# EFIS.net
KiCad netlist of a schematic drawn in EAGLE
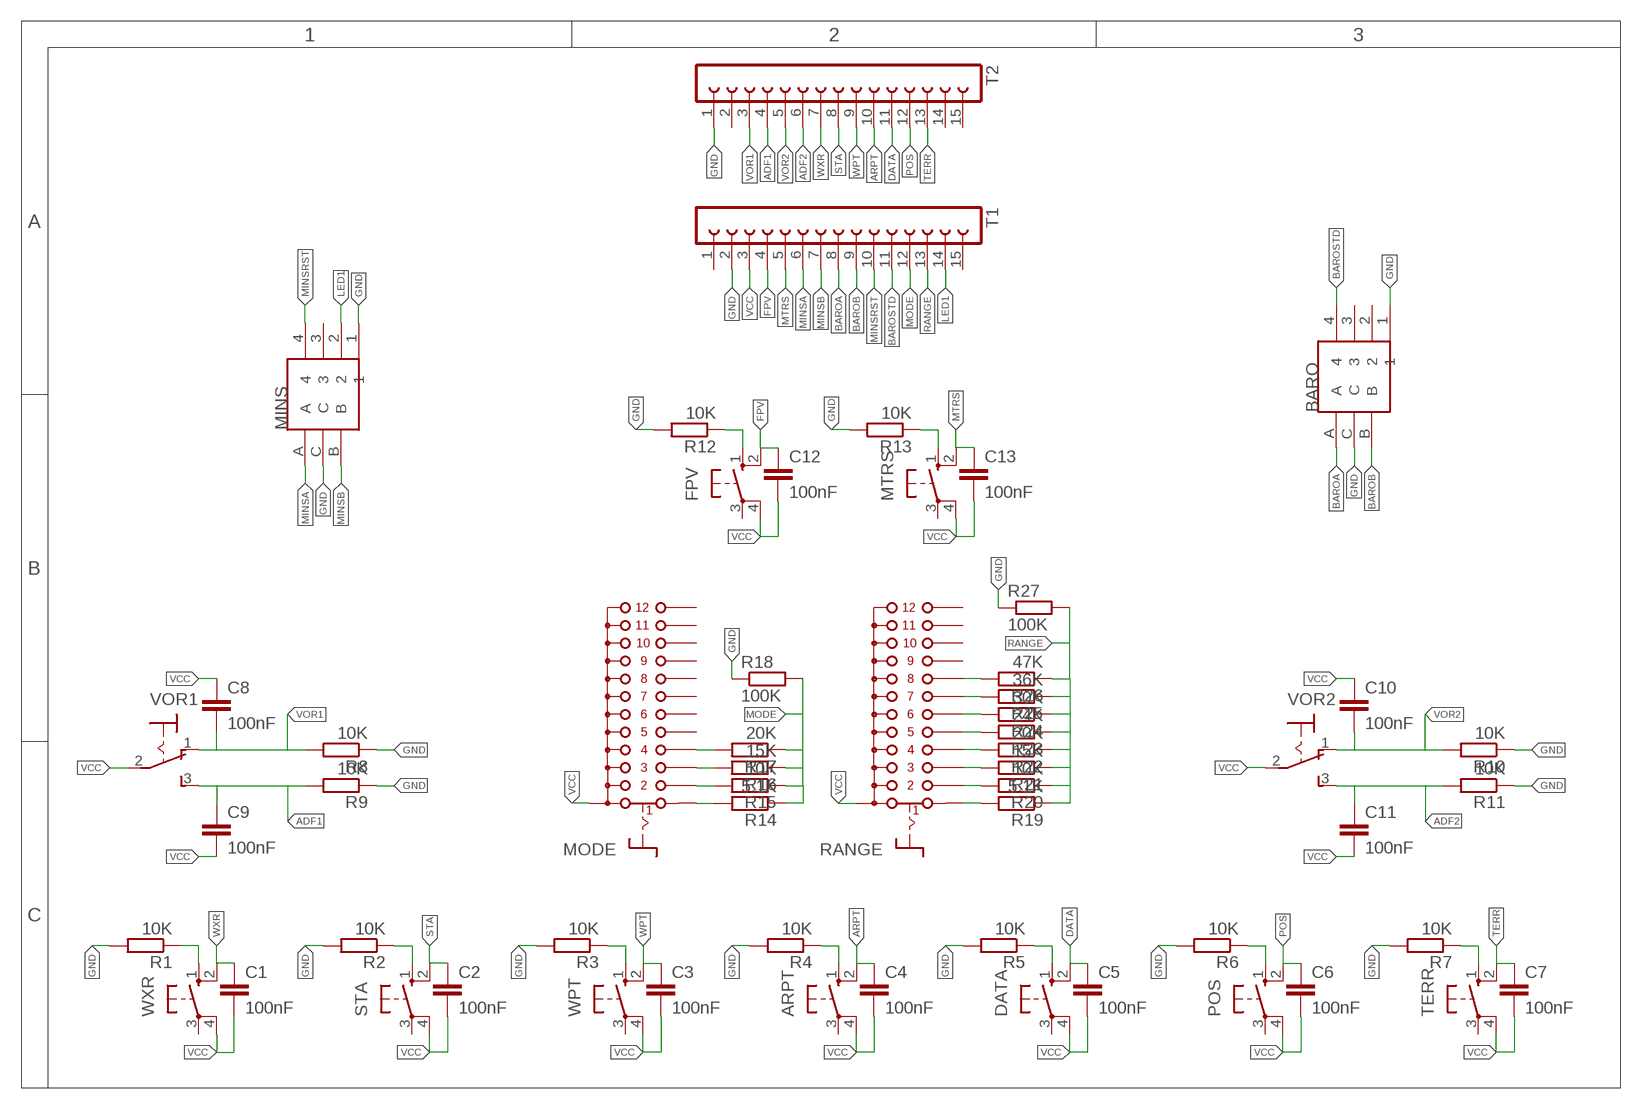
[diagram p0: schematic, sheet 1]

(export (version "E")
  (design (tool "Eeschema 10.0.6"))
  (components
    (comp (ref "ARPT")
      (value "10-XX")
      (footprint "eagle-import:B3F-10XX")
      (fields (field (name "MPN") "B3F-1000"))
      (libsource (lib "eagle-import") (part "10-XX"))
    )
    (comp (ref "BARO")
      (value "MERP12246GR")
      (footprint "eagle-import:MERP1224126")
      (libsource (lib "eagle-import") (part "MERP12246GR"))
    )
    (comp (ref "C1")
      (value "100nF")
      (footprint "eagle-import:C1206")
      (libsource (lib "eagle-import") (part "C-EUC1206"))
    )
    (comp (ref "C2")
      (value "100nF")
      (footprint "eagle-import:C1206")
      (libsource (lib "eagle-import") (part "C-EUC1206"))
    )
    (comp (ref "C3")
      (value "100nF")
      (footprint "eagle-import:C1206")
      (libsource (lib "eagle-import") (part "C-EUC1206"))
    )
    (comp (ref "C4")
      (value "100nF")
      (footprint "eagle-import:C1206")
      (libsource (lib "eagle-import") (part "C-EUC1206"))
    )
    (comp (ref "C5")
      (value "100nF")
      (footprint "eagle-import:C1206")
      (libsource (lib "eagle-import") (part "C-EUC1206"))
    )
    (comp (ref "C6")
      (value "100nF")
      (footprint "eagle-import:C1206")
      (libsource (lib "eagle-import") (part "C-EUC1206"))
    )
    (comp (ref "C7")
      (value "100nF")
      (footprint "eagle-import:C1206")
      (libsource (lib "eagle-import") (part "C-EUC1206"))
    )
    (comp (ref "C8")
      (value "100nF")
      (footprint "eagle-import:C1206")
      (libsource (lib "eagle-import") (part "C-EUC1206"))
    )
    (comp (ref "C9")
      (value "100nF")
      (footprint "eagle-import:C1206")
      (libsource (lib "eagle-import") (part "C-EUC1206"))
    )
    (comp (ref "C10")
      (value "100nF")
      (footprint "eagle-import:C1206")
      (libsource (lib "eagle-import") (part "C-EUC1206"))
    )
    (comp (ref "C11")
      (value "100nF")
      (footprint "eagle-import:C1206")
      (libsource (lib "eagle-import") (part "C-EUC1206"))
    )
    (comp (ref "C12")
      (value "100nF")
      (footprint "eagle-import:C1206")
      (libsource (lib "eagle-import") (part "C-EUC1206"))
    )
    (comp (ref "C13")
      (value "100nF")
      (footprint "eagle-import:C1206")
      (libsource (lib "eagle-import") (part "C-EUC1206"))
    )
    (comp (ref "DATA")
      (value "10-XX")
      (footprint "eagle-import:B3F-10XX")
      (fields (field (name "MPN") "B3F-1000"))
      (libsource (lib "eagle-import") (part "10-XX"))
    )
    (comp (ref "FPV")
      (value "10-XX")
      (footprint "eagle-import:B3F-10XX")
      (fields (field (name "MPN") "B3F-1000"))
      (libsource (lib "eagle-import") (part "10-XX"))
    )
    (comp (ref "MINS")
      (value "MERP12246GR")
      (footprint "eagle-import:MERP1224126")
      (libsource (lib "eagle-import") (part "MERP12246GR"))
    )
    (comp (ref "MODE")
      (value "CK101X12")
      (footprint "eagle-import:CK101X12")
      (libsource (lib "eagle-import") (part "CK101X12"))
    )
    (comp (ref "MTRS")
      (value "10-XX")
      (footprint "eagle-import:B3F-10XX")
      (fields (field (name "MPN") "B3F-1000"))
      (libsource (lib "eagle-import") (part "10-XX"))
    )
    (comp (ref "POS")
      (value "10-XX")
      (footprint "eagle-import:B3F-10XX")
      (fields (field (name "MPN") "B3F-1000"))
      (libsource (lib "eagle-import") (part "10-XX"))
    )
    (comp (ref "R1")
      (value "10K")
      (footprint "eagle-import:R1206")
      (libsource (lib "eagle-import") (part "R-EU_R1206"))
    )
    (comp (ref "R2")
      (value "10K")
      (footprint "eagle-import:R1206")
      (libsource (lib "eagle-import") (part "R-EU_R1206"))
    )
    (comp (ref "R3")
      (value "10K")
      (footprint "eagle-import:R1206")
      (libsource (lib "eagle-import") (part "R-EU_R1206"))
    )
    (comp (ref "R4")
      (value "10K")
      (footprint "eagle-import:R1206")
      (libsource (lib "eagle-import") (part "R-EU_R1206"))
    )
    (comp (ref "R5")
      (value "10K")
      (footprint "eagle-import:R1206")
      (libsource (lib "eagle-import") (part "R-EU_R1206"))
    )
    (comp (ref "R6")
      (value "10K")
      (footprint "eagle-import:R1206")
      (libsource (lib "eagle-import") (part "R-EU_R1206"))
    )
    (comp (ref "R7")
      (value "10K")
      (footprint "eagle-import:R1206")
      (libsource (lib "eagle-import") (part "R-EU_R1206"))
    )
    (comp (ref "R8")
      (value "10K")
      (footprint "eagle-import:R1206")
      (libsource (lib "eagle-import") (part "R-EU_R1206"))
    )
    (comp (ref "R9")
      (value "10K")
      (footprint "eagle-import:R1206")
      (libsource (lib "eagle-import") (part "R-EU_R1206"))
    )
    (comp (ref "R10")
      (value "10K")
      (footprint "eagle-import:R1206")
      (libsource (lib "eagle-import") (part "R-EU_R1206"))
    )
    (comp (ref "R11")
      (value "10K")
      (footprint "eagle-import:R1206")
      (libsource (lib "eagle-import") (part "R-EU_R1206"))
    )
    (comp (ref "R12")
      (value "10K")
      (footprint "eagle-import:R1206")
      (libsource (lib "eagle-import") (part "R-EU_R1206"))
    )
    (comp (ref "R13")
      (value "10K")
      (footprint "eagle-import:R1206")
      (libsource (lib "eagle-import") (part "R-EU_R1206"))
    )
    (comp (ref "R14")
      (value "5.1K")
      (footprint "eagle-import:R1206")
      (libsource (lib "eagle-import") (part "R-EU_R1206"))
    )
    (comp (ref "R15")
      (value "10K")
      (footprint "eagle-import:R1206")
      (libsource (lib "eagle-import") (part "R-EU_R1206"))
    )
    (comp (ref "R16")
      (value "15K")
      (footprint "eagle-import:R1206")
      (libsource (lib "eagle-import") (part "R-EU_R1206"))
    )
    (comp (ref "R17")
      (value "20K")
      (footprint "eagle-import:R1206")
      (libsource (lib "eagle-import") (part "R-EU_R1206"))
    )
    (comp (ref "R18")
      (value "100K")
      (footprint "eagle-import:R1206")
      (libsource (lib "eagle-import") (part "R-EU_R1206"))
    )
    (comp (ref "R19")
      (value "5.1K")
      (footprint "eagle-import:R1206")
      (libsource (lib "eagle-import") (part "R-EU_R1206"))
    )
    (comp (ref "R20")
      (value "10K")
      (footprint "eagle-import:R1206")
      (libsource (lib "eagle-import") (part "R-EU_R1206"))
    )
    (comp (ref "R21")
      (value "15K")
      (footprint "eagle-import:R1206")
      (libsource (lib "eagle-import") (part "R-EU_R1206"))
    )
    (comp (ref "R22")
      (value "20K")
      (footprint "eagle-import:R1206")
      (libsource (lib "eagle-import") (part "R-EU_R1206"))
    )
    (comp (ref "R23")
      (value "24K")
      (footprint "eagle-import:R1206")
      (libsource (lib "eagle-import") (part "R-EU_R1206"))
    )
    (comp (ref "R24")
      (value "30K")
      (footprint "eagle-import:R1206")
      (libsource (lib "eagle-import") (part "R-EU_R1206"))
    )
    (comp (ref "R25")
      (value "36K")
      (footprint "eagle-import:R1206")
      (libsource (lib "eagle-import") (part "R-EU_R1206"))
    )
    (comp (ref "R26")
      (value "47K")
      (footprint "eagle-import:R1206")
      (libsource (lib "eagle-import") (part "R-EU_R1206"))
    )
    (comp (ref "R27")
      (value "100K")
      (footprint "eagle-import:R1206")
      (libsource (lib "eagle-import") (part "R-EU_R1206"))
    )
    (comp (ref "RANGE")
      (value "CK101X12")
      (footprint "eagle-import:CK101X12")
      (libsource (lib "eagle-import") (part "CK101X12"))
    )
    (comp (ref "STA")
      (value "10-XX")
      (footprint "eagle-import:B3F-10XX")
      (fields (field (name "MPN") "B3F-1000"))
      (libsource (lib "eagle-import") (part "10-XX"))
    )
    (comp (ref "T1")
      (value "FE15-1")
      (footprint "eagle-import:FE15")
      (libsource (lib "eagle-import") (part "FE15-1"))
    )
    (comp (ref "T2")
      (value "FE15-1")
      (footprint "eagle-import:FE15")
      (libsource (lib "eagle-import") (part "FE15-1"))
    )
    (comp (ref "TERR")
      (value "10-XX")
      (footprint "eagle-import:B3F-10XX")
      (fields (field (name "MPN") "B3F-1000"))
      (libsource (lib "eagle-import") (part "10-XX"))
    )
    (comp (ref "VOR1")
      (value "320-916")
      (footprint "eagle-import:320-916")
      (libsource (lib "eagle-import") (part "320-916"))
    )
    (comp (ref "VOR2")
      (value "320-916")
      (footprint "eagle-import:320-916")
      (libsource (lib "eagle-import") (part "320-916"))
    )
    (comp (ref "WPT")
      (value "10-XX")
      (footprint "eagle-import:B3F-10XX")
      (fields (field (name "MPN") "B3F-1000"))
      (libsource (lib "eagle-import") (part "10-XX"))
    )
    (comp (ref "WXR")
      (value "10-XX")
      (footprint "eagle-import:B3F-10XX")
      (fields (field (name "MPN") "B3F-1000"))
      (libsource (lib "eagle-import") (part "10-XX"))
    )
  )
  (nets
    (net (code "1") (name "ADF1") (class "Default")
      (node (ref "C9") (pin "1") (pinfunction "1_1") (pintype "passive"))
      (node (ref "R9") (pin "2") (pinfunction "2_2") (pintype "passive"))
      (node (ref "T2") (pin "4") (pinfunction "4_4") (pintype "passive"))
      (node (ref "VOR1") (pin "3") (pinfunction "S_3") (pintype "passive"))
    )
    (net (code "2") (name "ADF2") (class "Default")
      (node (ref "C11") (pin "1") (pinfunction "1_1") (pintype "passive"))
      (node (ref "R11") (pin "2") (pinfunction "2_2") (pintype "passive"))
      (node (ref "T2") (pin "6") (pinfunction "6_6") (pintype "passive"))
      (node (ref "VOR2") (pin "3") (pinfunction "S_3") (pintype "passive"))
    )
    (net (code "3") (name "ARPT") (class "Default")
      (node (ref "ARPT") (pin "2") (pinfunction "S1_2") (pintype "passive"))
      (node (ref "C4") (pin "1") (pinfunction "1_1") (pintype "passive"))
      (node (ref "T2") (pin "10") (pinfunction "10_10") (pintype "passive"))
    )
    (net (code "4") (name "BAROA") (class "Default")
      (node (ref "BARO") (pin "A") (pinfunction "A_A") (pintype "bidirectional"))
      (node (ref "T1") (pin "8") (pinfunction "8_8") (pintype "passive"))
    )
    (net (code "5") (name "BAROB") (class "Default")
      (node (ref "BARO") (pin "B") (pinfunction "B_B") (pintype "bidirectional"))
      (node (ref "T1") (pin "9") (pinfunction "9_9") (pintype "passive"))
    )
    (net (code "6") (name "BAROSTD") (class "Default")
      (node (ref "BARO") (pin "4") (pinfunction "4_4") (pintype "bidirectional"))
      (node (ref "T1") (pin "11") (pinfunction "11_11") (pintype "passive"))
    )
    (net (code "7") (name "DATA") (class "Default")
      (node (ref "C5") (pin "1") (pinfunction "1_1") (pintype "passive"))
      (node (ref "DATA") (pin "2") (pinfunction "S1_2") (pintype "passive"))
      (node (ref "T2") (pin "11") (pinfunction "11_11") (pintype "passive"))
    )
    (net (code "8") (name "FPV") (class "Default")
      (node (ref "C12") (pin "1") (pinfunction "1_1") (pintype "passive"))
      (node (ref "FPV") (pin "2") (pinfunction "S1_2") (pintype "passive"))
      (node (ref "T1") (pin "4") (pinfunction "4_4") (pintype "passive"))
    )
    (net (code "9") (name "GND") (class "Default")
      (node (ref "BARO") (pin "1") (pinfunction "1_1") (pintype "bidirectional"))
      (node (ref "BARO") (pin "C") (pinfunction "C_C") (pintype "bidirectional"))
      (node (ref "MINS") (pin "1") (pinfunction "1_1") (pintype "bidirectional"))
      (node (ref "MINS") (pin "C") (pinfunction "C_C") (pintype "bidirectional"))
      (node (ref "R1") (pin "2") (pinfunction "2_2") (pintype "passive"))
      (node (ref "R10") (pin "1") (pinfunction "1_1") (pintype "passive"))
      (node (ref "R11") (pin "1") (pinfunction "1_1") (pintype "passive"))
      (node (ref "R12") (pin "2") (pinfunction "2_2") (pintype "passive"))
      (node (ref "R13") (pin "2") (pinfunction "2_2") (pintype "passive"))
      (node (ref "R18") (pin "1") (pinfunction "1_1") (pintype "passive"))
      (node (ref "R2") (pin "2") (pinfunction "2_2") (pintype "passive"))
      (node (ref "R27") (pin "1") (pinfunction "1_1") (pintype "passive"))
      (node (ref "R3") (pin "2") (pinfunction "2_2") (pintype "passive"))
      (node (ref "R4") (pin "2") (pinfunction "2_2") (pintype "passive"))
      (node (ref "R5") (pin "2") (pinfunction "2_2") (pintype "passive"))
      (node (ref "R6") (pin "2") (pinfunction "2_2") (pintype "passive"))
      (node (ref "R7") (pin "2") (pinfunction "2_2") (pintype "passive"))
      (node (ref "R8") (pin "1") (pinfunction "1_1") (pintype "passive"))
      (node (ref "R9") (pin "1") (pinfunction "1_1") (pintype "passive"))
      (node (ref "T1") (pin "2") (pinfunction "2_2") (pintype "passive"))
      (node (ref "T2") (pin "1") (pinfunction "1_1") (pintype "passive"))
    )
    (net (code "10") (name "LED1") (class "Default")
      (node (ref "MINS") (pin "2") (pinfunction "2_2") (pintype "bidirectional"))
      (node (ref "T1") (pin "14") (pinfunction "14_14") (pintype "passive"))
    )
    (net (code "11") (name "MINSA") (class "Default")
      (node (ref "MINS") (pin "A") (pinfunction "A_A") (pintype "bidirectional"))
      (node (ref "T1") (pin "6") (pinfunction "6_6") (pintype "passive"))
    )
    (net (code "12") (name "MINSB") (class "Default")
      (node (ref "MINS") (pin "B") (pinfunction "B_B") (pintype "bidirectional"))
      (node (ref "T1") (pin "7") (pinfunction "7_7") (pintype "passive"))
    )
    (net (code "13") (name "MINSRST") (class "Default")
      (node (ref "MINS") (pin "4") (pinfunction "4_4") (pintype "bidirectional"))
      (node (ref "T1") (pin "10") (pinfunction "10_10") (pintype "passive"))
    )
    (net (code "14") (name "MODE") (class "Default")
      (node (ref "R14") (pin "1") (pinfunction "1_1") (pintype "passive"))
      (node (ref "R15") (pin "1") (pinfunction "1_1") (pintype "passive"))
      (node (ref "R16") (pin "1") (pinfunction "1_1") (pintype "passive"))
      (node (ref "R17") (pin "1") (pinfunction "1_1") (pintype "passive"))
      (node (ref "R18") (pin "2") (pinfunction "2_2") (pintype "passive"))
      (node (ref "T1") (pin "12") (pinfunction "12_12") (pintype "passive"))
    )
    (net (code "15") (name "MTRS") (class "Default")
      (node (ref "C13") (pin "1") (pinfunction "1_1") (pintype "passive"))
      (node (ref "MTRS") (pin "2") (pinfunction "S1_2") (pintype "passive"))
      (node (ref "T1") (pin "5") (pinfunction "5_5") (pintype "passive"))
    )
    (net (code "16") (name "Net-(ARPT-S)") (class "Default")
      (node (ref "ARPT") (pin "1") (pinfunction "S_1") (pintype "passive"))
      (node (ref "R4") (pin "1") (pinfunction "1_1") (pintype "passive"))
    )
    (net (code "17") (name "Net-(DATA-S)") (class "Default")
      (node (ref "DATA") (pin "1") (pinfunction "S_1") (pintype "passive"))
      (node (ref "R5") (pin "1") (pinfunction "1_1") (pintype "passive"))
    )
    (net (code "18") (name "Net-(FPV-S)") (class "Default")
      (node (ref "FPV") (pin "1") (pinfunction "S_1") (pintype "passive"))
      (node (ref "R12") (pin "1") (pinfunction "1_1") (pintype "passive"))
    )
    (net (code "19") (name "Net-(MODE-Pad1)") (class "Default")
      (node (ref "MODE") (pin "1") (pinfunction "1_1") (pintype "passive"))
      (node (ref "R14") (pin "2") (pinfunction "2_2") (pintype "passive"))
    )
    (net (code "20") (name "Net-(MODE-Pad2)") (class "Default")
      (node (ref "MODE") (pin "2") (pinfunction "2_2") (pintype "passive"))
      (node (ref "R15") (pin "2") (pinfunction "2_2") (pintype "passive"))
    )
    (net (code "21") (name "Net-(MODE-Pad3)") (class "Default")
      (node (ref "MODE") (pin "3") (pinfunction "3_3") (pintype "passive"))
      (node (ref "R16") (pin "2") (pinfunction "2_2") (pintype "passive"))
    )
    (net (code "22") (name "Net-(MODE-Pad4)") (class "Default")
      (node (ref "MODE") (pin "4") (pinfunction "4_4") (pintype "passive"))
      (node (ref "R17") (pin "2") (pinfunction "2_2") (pintype "passive"))
    )
    (net (code "23") (name "Net-(MTRS-S)") (class "Default")
      (node (ref "MTRS") (pin "1") (pinfunction "S_1") (pintype "passive"))
      (node (ref "R13") (pin "1") (pinfunction "1_1") (pintype "passive"))
    )
    (net (code "24") (name "Net-(POS-S)") (class "Default")
      (node (ref "POS") (pin "1") (pinfunction "S_1") (pintype "passive"))
      (node (ref "R6") (pin "1") (pinfunction "1_1") (pintype "passive"))
    )
    (net (code "25") (name "Net-(R19-Pad2)") (class "Default")
      (node (ref "R19") (pin "2") (pinfunction "2_2") (pintype "passive"))
      (node (ref "RANGE") (pin "1") (pinfunction "1_1") (pintype "passive"))
    )
    (net (code "26") (name "Net-(R20-Pad2)") (class "Default")
      (node (ref "R20") (pin "2") (pinfunction "2_2") (pintype "passive"))
      (node (ref "RANGE") (pin "2") (pinfunction "2_2") (pintype "passive"))
    )
    (net (code "27") (name "Net-(R21-Pad2)") (class "Default")
      (node (ref "R21") (pin "2") (pinfunction "2_2") (pintype "passive"))
      (node (ref "RANGE") (pin "3") (pinfunction "3_3") (pintype "passive"))
    )
    (net (code "28") (name "Net-(R22-Pad2)") (class "Default")
      (node (ref "R22") (pin "2") (pinfunction "2_2") (pintype "passive"))
      (node (ref "RANGE") (pin "4") (pinfunction "4_4") (pintype "passive"))
    )
    (net (code "29") (name "Net-(R23-Pad2)") (class "Default")
      (node (ref "R23") (pin "2") (pinfunction "2_2") (pintype "passive"))
      (node (ref "RANGE") (pin "5") (pinfunction "5_5") (pintype "passive"))
    )
    (net (code "30") (name "Net-(R24-Pad2)") (class "Default")
      (node (ref "R24") (pin "2") (pinfunction "2_2") (pintype "passive"))
      (node (ref "RANGE") (pin "6") (pinfunction "6_6") (pintype "passive"))
    )
    (net (code "31") (name "Net-(R25-Pad2)") (class "Default")
      (node (ref "R25") (pin "2") (pinfunction "2_2") (pintype "passive"))
      (node (ref "RANGE") (pin "7") (pinfunction "7_7") (pintype "passive"))
    )
    (net (code "32") (name "Net-(R26-Pad2)") (class "Default")
      (node (ref "R26") (pin "2") (pinfunction "2_2") (pintype "passive"))
      (node (ref "RANGE") (pin "8") (pinfunction "8_8") (pintype "passive"))
    )
    (net (code "33") (name "Net-(STA-S)") (class "Default")
      (node (ref "R2") (pin "1") (pinfunction "1_1") (pintype "passive"))
      (node (ref "STA") (pin "1") (pinfunction "S_1") (pintype "passive"))
    )
    (net (code "34") (name "Net-(TERR-S)") (class "Default")
      (node (ref "R7") (pin "1") (pinfunction "1_1") (pintype "passive"))
      (node (ref "TERR") (pin "1") (pinfunction "S_1") (pintype "passive"))
    )
    (net (code "35") (name "Net-(WPT-S)") (class "Default")
      (node (ref "R3") (pin "1") (pinfunction "1_1") (pintype "passive"))
      (node (ref "WPT") (pin "1") (pinfunction "S_1") (pintype "passive"))
    )
    (net (code "36") (name "Net-(WXR-S)") (class "Default")
      (node (ref "R1") (pin "1") (pinfunction "1_1") (pintype "passive"))
      (node (ref "WXR") (pin "1") (pinfunction "S_1") (pintype "passive"))
    )
    (net (code "37") (name "POS") (class "Default")
      (node (ref "C6") (pin "1") (pinfunction "1_1") (pintype "passive"))
      (node (ref "POS") (pin "2") (pinfunction "S1_2") (pintype "passive"))
      (node (ref "T2") (pin "12") (pinfunction "12_12") (pintype "passive"))
    )
    (net (code "38") (name "RANGE") (class "Default")
      (node (ref "R19") (pin "1") (pinfunction "1_1") (pintype "passive"))
      (node (ref "R20") (pin "1") (pinfunction "1_1") (pintype "passive"))
      (node (ref "R21") (pin "1") (pinfunction "1_1") (pintype "passive"))
      (node (ref "R22") (pin "1") (pinfunction "1_1") (pintype "passive"))
      (node (ref "R23") (pin "1") (pinfunction "1_1") (pintype "passive"))
      (node (ref "R24") (pin "1") (pinfunction "1_1") (pintype "passive"))
      (node (ref "R25") (pin "1") (pinfunction "1_1") (pintype "passive"))
      (node (ref "R26") (pin "1") (pinfunction "1_1") (pintype "passive"))
      (node (ref "R27") (pin "2") (pinfunction "2_2") (pintype "passive"))
      (node (ref "T1") (pin "13") (pinfunction "13_13") (pintype "passive"))
    )
    (net (code "39") (name "STA") (class "Default")
      (node (ref "C2") (pin "1") (pinfunction "1_1") (pintype "passive"))
      (node (ref "STA") (pin "2") (pinfunction "S1_2") (pintype "passive"))
      (node (ref "T2") (pin "8") (pinfunction "8_8") (pintype "passive"))
    )
    (net (code "40") (name "TERR") (class "Default")
      (node (ref "C7") (pin "1") (pinfunction "1_1") (pintype "passive"))
      (node (ref "T2") (pin "13") (pinfunction "13_13") (pintype "passive"))
      (node (ref "TERR") (pin "2") (pinfunction "S1_2") (pintype "passive"))
    )
    (net (code "41") (name "VCC") (class "Default")
      (node (ref "ARPT") (pin "4") (pinfunction "P1_4") (pintype "passive"))
      (node (ref "C1") (pin "2") (pinfunction "2_2") (pintype "passive"))
      (node (ref "C10") (pin "1") (pinfunction "1_1") (pintype "passive"))
      (node (ref "C11") (pin "2") (pinfunction "2_2") (pintype "passive"))
      (node (ref "C12") (pin "2") (pinfunction "2_2") (pintype "passive"))
      (node (ref "C13") (pin "2") (pinfunction "2_2") (pintype "passive"))
      (node (ref "C2") (pin "2") (pinfunction "2_2") (pintype "passive"))
      (node (ref "C3") (pin "2") (pinfunction "2_2") (pintype "passive"))
      (node (ref "C4") (pin "2") (pinfunction "2_2") (pintype "passive"))
      (node (ref "C5") (pin "2") (pinfunction "2_2") (pintype "passive"))
      (node (ref "C6") (pin "2") (pinfunction "2_2") (pintype "passive"))
      (node (ref "C7") (pin "2") (pinfunction "2_2") (pintype "passive"))
      (node (ref "C8") (pin "1") (pinfunction "1_1") (pintype "passive"))
      (node (ref "C9") (pin "2") (pinfunction "2_2") (pintype "passive"))
      (node (ref "DATA") (pin "4") (pinfunction "P1_4") (pintype "passive"))
      (node (ref "FPV") (pin "4") (pinfunction "P1_4") (pintype "passive"))
      (node (ref "MODE") (pin "A") (pinfunction "A_A") (pintype "passive"))
      (node (ref "MTRS") (pin "4") (pinfunction "P1_4") (pintype "passive"))
      (node (ref "POS") (pin "4") (pinfunction "P1_4") (pintype "passive"))
      (node (ref "RANGE") (pin "A") (pinfunction "A_A") (pintype "passive"))
      (node (ref "STA") (pin "4") (pinfunction "P1_4") (pintype "passive"))
      (node (ref "T1") (pin "3") (pinfunction "3_3") (pintype "passive"))
      (node (ref "TERR") (pin "4") (pinfunction "P1_4") (pintype "passive"))
      (node (ref "VOR1") (pin "2") (pinfunction "P_2") (pintype "passive"))
      (node (ref "VOR2") (pin "2") (pinfunction "P_2") (pintype "passive"))
      (node (ref "WPT") (pin "4") (pinfunction "P1_4") (pintype "passive"))
      (node (ref "WXR") (pin "4") (pinfunction "P1_4") (pintype "passive"))
    )
    (net (code "42") (name "VOR1") (class "Default")
      (node (ref "C8") (pin "2") (pinfunction "2_2") (pintype "passive"))
      (node (ref "R8") (pin "2") (pinfunction "2_2") (pintype "passive"))
      (node (ref "T2") (pin "3") (pinfunction "3_3") (pintype "passive"))
      (node (ref "VOR1") (pin "1") (pinfunction "O_1") (pintype "passive"))
    )
    (net (code "43") (name "VOR2") (class "Default")
      (node (ref "C10") (pin "2") (pinfunction "2_2") (pintype "passive"))
      (node (ref "R10") (pin "2") (pinfunction "2_2") (pintype "passive"))
      (node (ref "T2") (pin "5") (pinfunction "5_5") (pintype "passive"))
      (node (ref "VOR2") (pin "1") (pinfunction "O_1") (pintype "passive"))
    )
    (net (code "44") (name "WPT") (class "Default")
      (node (ref "C3") (pin "1") (pinfunction "1_1") (pintype "passive"))
      (node (ref "T2") (pin "9") (pinfunction "9_9") (pintype "passive"))
      (node (ref "WPT") (pin "2") (pinfunction "S1_2") (pintype "passive"))
    )
    (net (code "45") (name "WXR") (class "Default")
      (node (ref "C1") (pin "1") (pinfunction "1_1") (pintype "passive"))
      (node (ref "T2") (pin "7") (pinfunction "7_7") (pintype "passive"))
      (node (ref "WXR") (pin "2") (pinfunction "S1_2") (pintype "passive"))
    )
    (net (code "46") (name "unconnected-(ARPT-P-Pad3)") (class "Default")
      (node (ref "ARPT") (pin "3") (pinfunction "P_3") (pintype "passive"))
    )
    (net (code "47") (name "unconnected-(BARO-Pad2)") (class "Default")
      (node (ref "BARO") (pin "2") (pinfunction "2_2") (pintype "bidirectional"))
    )
    (net (code "48") (name "unconnected-(BARO-Pad3)") (class "Default")
      (node (ref "BARO") (pin "3") (pinfunction "3_3") (pintype "bidirectional"))
    )
    (net (code "49") (name "unconnected-(DATA-P-Pad3)") (class "Default")
      (node (ref "DATA") (pin "3") (pinfunction "P_3") (pintype "passive"))
    )
    (net (code "50") (name "unconnected-(FPV-P-Pad3)") (class "Default")
      (node (ref "FPV") (pin "3") (pinfunction "P_3") (pintype "passive"))
    )
    (net (code "51") (name "unconnected-(MINS-Pad3)") (class "Default")
      (node (ref "MINS") (pin "3") (pinfunction "3_3") (pintype "bidirectional"))
    )
    (net (code "52") (name "unconnected-(MODE-Pad5)") (class "Default")
      (node (ref "MODE") (pin "5") (pinfunction "5_5") (pintype "passive"))
    )
    (net (code "53") (name "unconnected-(MODE-Pad6)") (class "Default")
      (node (ref "MODE") (pin "6") (pinfunction "6_6") (pintype "passive"))
    )
    (net (code "54") (name "unconnected-(MODE-Pad7)") (class "Default")
      (node (ref "MODE") (pin "7") (pinfunction "7_7") (pintype "passive"))
    )
    (net (code "55") (name "unconnected-(MODE-Pad8)") (class "Default")
      (node (ref "MODE") (pin "8") (pinfunction "8_8") (pintype "passive"))
    )
    (net (code "56") (name "unconnected-(MODE-Pad9)") (class "Default")
      (node (ref "MODE") (pin "9") (pinfunction "9_9") (pintype "passive"))
    )
    (net (code "57") (name "unconnected-(MODE-Pad10)") (class "Default")
      (node (ref "MODE") (pin "10") (pinfunction "10_10") (pintype "passive"))
    )
    (net (code "58") (name "unconnected-(MODE-Pad11)") (class "Default")
      (node (ref "MODE") (pin "11") (pinfunction "11_11") (pintype "passive"))
    )
    (net (code "59") (name "unconnected-(MODE-Pad12)") (class "Default")
      (node (ref "MODE") (pin "12") (pinfunction "12_12") (pintype "passive"))
    )
    (net (code "60") (name "unconnected-(MTRS-P-Pad3)") (class "Default")
      (node (ref "MTRS") (pin "3") (pinfunction "P_3") (pintype "passive"))
    )
    (net (code "61") (name "unconnected-(POS-P-Pad3)") (class "Default")
      (node (ref "POS") (pin "3") (pinfunction "P_3") (pintype "passive"))
    )
    (net (code "62") (name "unconnected-(RANGE-Pad9)") (class "Default")
      (node (ref "RANGE") (pin "9") (pinfunction "9_9") (pintype "passive"))
    )
    (net (code "63") (name "unconnected-(RANGE-Pad10)") (class "Default")
      (node (ref "RANGE") (pin "10") (pinfunction "10_10") (pintype "passive"))
    )
    (net (code "64") (name "unconnected-(RANGE-Pad11)") (class "Default")
      (node (ref "RANGE") (pin "11") (pinfunction "11_11") (pintype "passive"))
    )
    (net (code "65") (name "unconnected-(RANGE-Pad12)") (class "Default")
      (node (ref "RANGE") (pin "12") (pinfunction "12_12") (pintype "passive"))
    )
    (net (code "66") (name "unconnected-(STA-P-Pad3)") (class "Default")
      (node (ref "STA") (pin "3") (pinfunction "P_3") (pintype "passive"))
    )
    (net (code "67") (name "unconnected-(T1-Pad1)") (class "Default")
      (node (ref "T1") (pin "1") (pinfunction "1_1") (pintype "passive"))
    )
    (net (code "68") (name "unconnected-(T1-Pad15)") (class "Default")
      (node (ref "T1") (pin "15") (pinfunction "15_15") (pintype "passive"))
    )
    (net (code "69") (name "unconnected-(T2-Pad2)") (class "Default")
      (node (ref "T2") (pin "2") (pinfunction "2_2") (pintype "passive"))
    )
    (net (code "70") (name "unconnected-(T2-Pad14)") (class "Default")
      (node (ref "T2") (pin "14") (pinfunction "14_14") (pintype "passive"))
    )
    (net (code "71") (name "unconnected-(T2-Pad15)") (class "Default")
      (node (ref "T2") (pin "15") (pinfunction "15_15") (pintype "passive"))
    )
    (net (code "72") (name "unconnected-(TERR-P-Pad3)") (class "Default")
      (node (ref "TERR") (pin "3") (pinfunction "P_3") (pintype "passive"))
    )
    (net (code "73") (name "unconnected-(WPT-P-Pad3)") (class "Default")
      (node (ref "WPT") (pin "3") (pinfunction "P_3") (pintype "passive"))
    )
    (net (code "74") (name "unconnected-(WXR-P-Pad3)") (class "Default")
      (node (ref "WXR") (pin "3") (pinfunction "P_3") (pintype "passive"))
    )
  )
)
